# led_schematic.net
KiCad netlist of a schematic drawn in Altium Designer
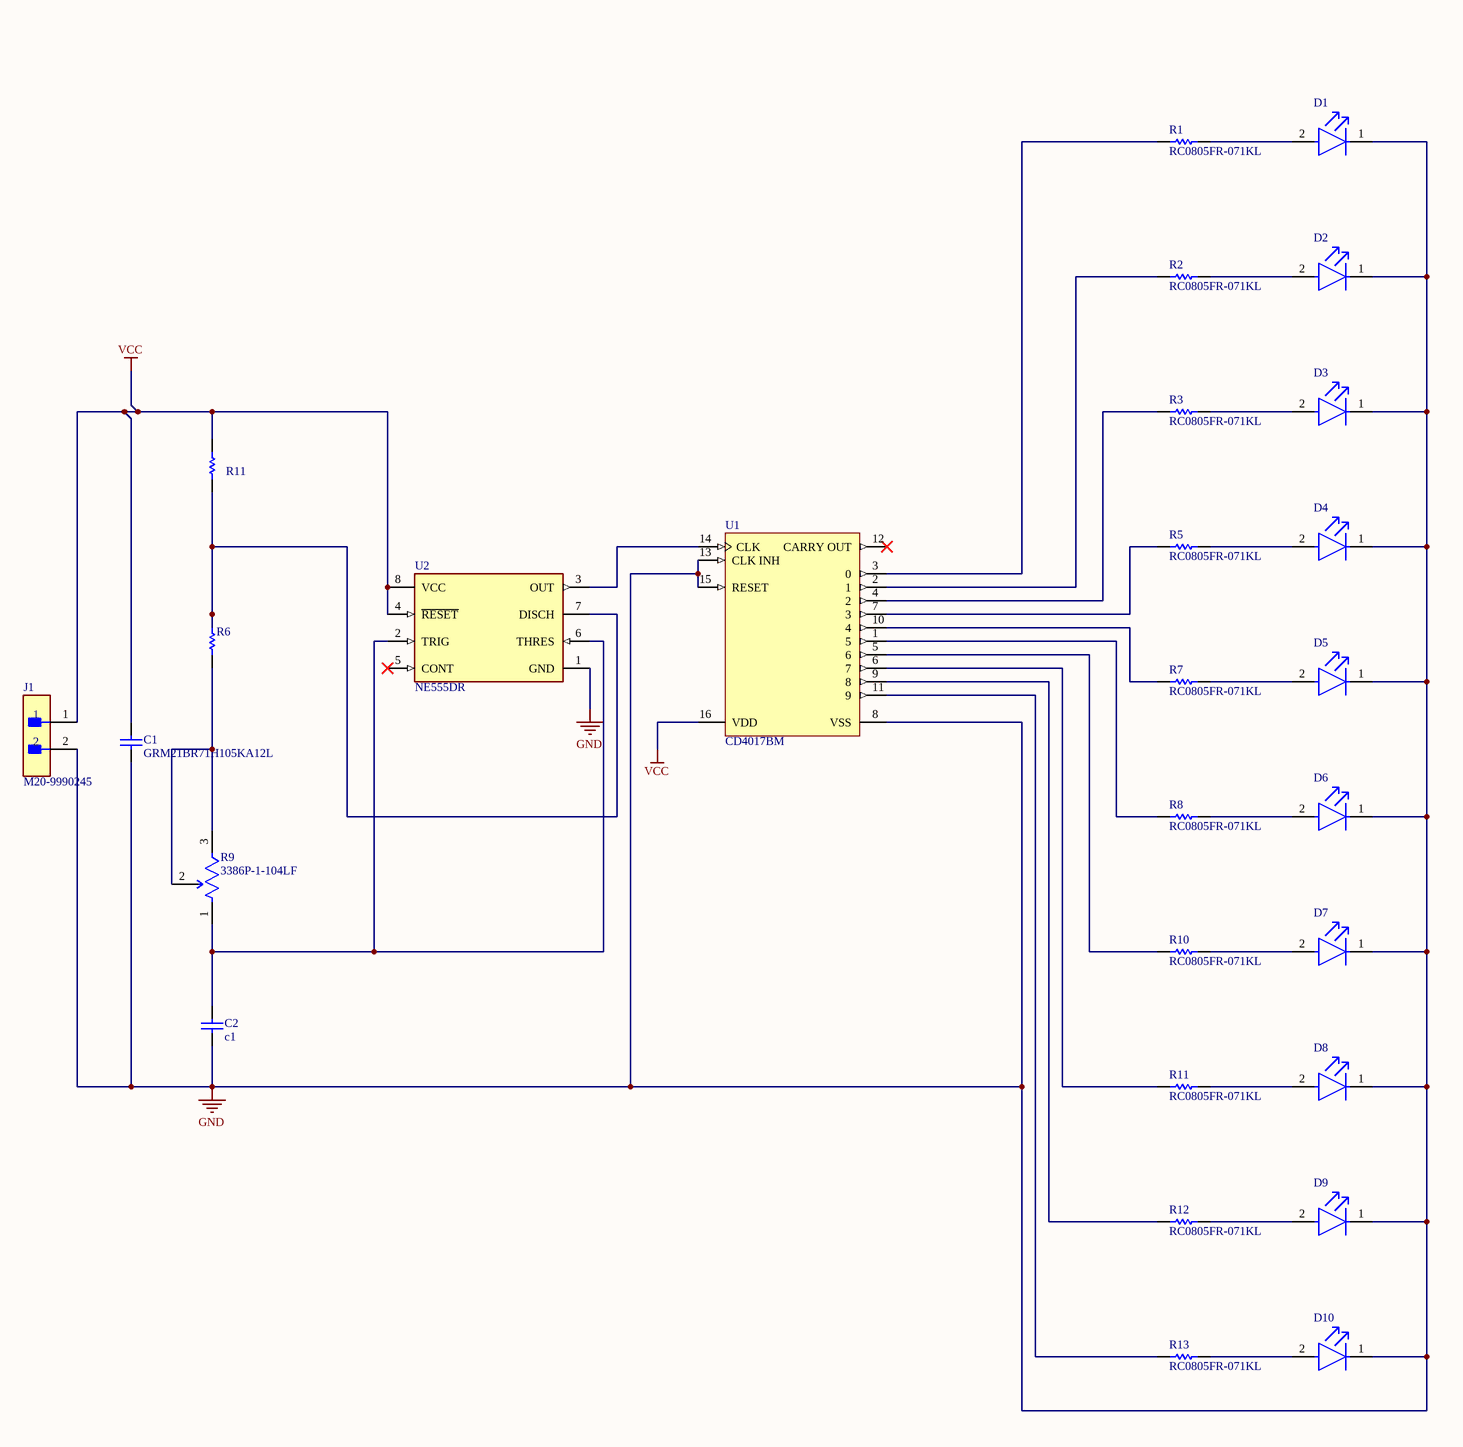
[diagram p0: led_schematic.SchDoc, right]

(export (version "E")
  (design (tool "Eeschema 10.0.6"))
  (components
    (comp (ref "C1")
      (value "GRM21BR71H105KA12L")
      (footprint "CAPC2013X135X45LL10T25")
      (fields (field (name "MANUFACTURER") "Murata"))
      (libsource (lib "Altium Content Vault") (part "CAP"))
    )
    (comp (ref "C2")
      (value "c1")
      (footprint "CAPC2013X135X45LL10T25")
      (fields (field (name "MANUFACTURER") "Murata") (field (name "PART NUMBER") "GRM21BR71H105KA12L"))
      (libsource (lib "Altium Content Vault") (part "CAP"))
    )
    (comp (ref "D1")
      (value "HLMP-1719")
      (footprint "FP-HLMP-1719-MFG")
      (description "LED YELLOW DIFFUSED T-1 T/H")
      (fields
        (field (name "MANUFACTURER") "Broadcom")
        (field (name "OCTOPART") "https://octopart.com/hlmp-1719-broadcom-71130405")
      )
      (libsource (lib "Altium Content Vault") (part "8706943c75ba83719d021d2fdc84c58"))
    )
    (comp (ref "D2")
      (value "HLMP-1719")
      (footprint "FP-HLMP-1719-MFG")
      (description "LED YELLOW DIFFUSED T-1 T/H")
      (fields
        (field (name "MANUFACTURER") "Broadcom")
        (field (name "OCTOPART") "https://octopart.com/hlmp-1719-broadcom-71130405")
      )
      (libsource (lib "Altium Content Vault") (part "8706943c75ba83719d021d2fdc84c58"))
    )
    (comp (ref "D3")
      (value "HLMP-1719")
      (footprint "FP-HLMP-1719-MFG")
      (description "LED YELLOW DIFFUSED T-1 T/H")
      (fields
        (field (name "MANUFACTURER") "Broadcom")
        (field (name "OCTOPART") "https://octopart.com/hlmp-1719-broadcom-71130405")
      )
      (libsource (lib "Altium Content Vault") (part "8706943c75ba83719d021d2fdc84c58"))
    )
    (comp (ref "D4")
      (value "HLMP-1719")
      (footprint "FP-HLMP-1719-MFG")
      (description "LED YELLOW DIFFUSED T-1 T/H")
      (fields
        (field (name "MANUFACTURER") "Broadcom")
        (field (name "OCTOPART") "https://octopart.com/hlmp-1719-broadcom-71130405")
      )
      (libsource (lib "Altium Content Vault") (part "8706943c75ba83719d021d2fdc84c58"))
    )
    (comp (ref "D5")
      (value "HLMP-1719")
      (footprint "FP-HLMP-1719-MFG")
      (description "LED YELLOW DIFFUSED T-1 T/H")
      (fields
        (field (name "MANUFACTURER") "Broadcom")
        (field (name "OCTOPART") "https://octopart.com/hlmp-1719-broadcom-71130405")
      )
      (libsource (lib "Altium Content Vault") (part "8706943c75ba83719d021d2fdc84c58"))
    )
    (comp (ref "D6")
      (value "HLMP-1719")
      (footprint "FP-HLMP-1719-MFG")
      (description "LED YELLOW DIFFUSED T-1 T/H")
      (fields
        (field (name "MANUFACTURER") "Broadcom")
        (field (name "OCTOPART") "https://octopart.com/hlmp-1719-broadcom-71130405")
      )
      (libsource (lib "Altium Content Vault") (part "8706943c75ba83719d021d2fdc84c58"))
    )
    (comp (ref "D7")
      (value "HLMP-1719")
      (footprint "FP-HLMP-1719-MFG")
      (description "LED YELLOW DIFFUSED T-1 T/H")
      (fields
        (field (name "MANUFACTURER") "Broadcom")
        (field (name "OCTOPART") "https://octopart.com/hlmp-1719-broadcom-71130405")
      )
      (libsource (lib "Altium Content Vault") (part "8706943c75ba83719d021d2fdc84c58"))
    )
    (comp (ref "D8")
      (value "HLMP-1719")
      (footprint "FP-HLMP-1719-MFG")
      (description "LED YELLOW DIFFUSED T-1 T/H")
      (fields
        (field (name "MANUFACTURER") "Broadcom")
        (field (name "OCTOPART") "https://octopart.com/hlmp-1719-broadcom-71130405")
      )
      (libsource (lib "Altium Content Vault") (part "8706943c75ba83719d021d2fdc84c58"))
    )
    (comp (ref "D9")
      (value "HLMP-1719")
      (footprint "FP-HLMP-1719-MFG")
      (description "LED YELLOW DIFFUSED T-1 T/H")
      (fields
        (field (name "MANUFACTURER") "Broadcom")
        (field (name "OCTOPART") "https://octopart.com/hlmp-1719-broadcom-71130405")
      )
      (libsource (lib "Altium Content Vault") (part "8706943c75ba83719d021d2fdc84c58"))
    )
    (comp (ref "D10")
      (value "HLMP-1719")
      (footprint "FP-HLMP-1719-MFG")
      (description "LED YELLOW DIFFUSED T-1 T/H")
      (fields
        (field (name "MANUFACTURER") "Broadcom")
        (field (name "OCTOPART") "https://octopart.com/hlmp-1719-broadcom-71130405")
      )
      (libsource (lib "Altium Content Vault") (part "8706943c75ba83719d021d2fdc84c58"))
    )
    (comp (ref "J1")
      (value "M20-9990245")
      (footprint "FP-M20-9990245-MFG")
      (description "CONN HEADER VERT 2POS 2.54MM")
      (fields (field (name "VOLTAGE") "50V"))
      (libsource (lib "Altium Content Vault") (part "3bc925449376181038e59eaffc5286c"))
    )
    (comp (ref "R1")
      (value "RC0805FR-071KL")
      (footprint "RESC2013X60X35ML10T20")
      (description "Chip Resistor, 1 KOhm, +/- 1%, 125 mW, -55 to 155 degC, 0805 (2012 Metric), RoHS, Tape and Reel")
      (fields (field (name "TOLERANCE") "1%") (field (name "MANUFACTURER") "Yageo"))
      (libsource (lib "Altium Content Vault") (part "RES-2"))
    )
    (comp (ref "R2")
      (value "RC0805FR-071KL")
      (footprint "RESC2013X60X35ML10T20")
      (description "Chip Resistor, 1 KOhm, +/- 1%, 125 mW, -55 to 155 degC, 0805 (2012 Metric), RoHS, Tape and Reel")
      (fields (field (name "TOLERANCE") "1%") (field (name "MANUFACTURER") "Yageo"))
      (libsource (lib "Altium Content Vault") (part "RES-2"))
    )
    (comp (ref "R3")
      (value "RC0805FR-071KL")
      (footprint "RESC2013X60X35ML10T20")
      (description "Chip Resistor, 1 KOhm, +/- 1%, 125 mW, -55 to 155 degC, 0805 (2012 Metric), RoHS, Tape and Reel")
      (fields (field (name "TOLERANCE") "1%") (field (name "MANUFACTURER") "Yageo"))
      (libsource (lib "Altium Content Vault") (part "RES-2"))
    )
    (comp (ref "R4")
      (value "R11")
      (footprint "RESC2013X60X35ML10T20")
      (description "Chip Resistor, 1 KOhm, +/- 1%, 125 mW, -55 to 155 degC, 0805 (2012 Metric), RoHS, Tape and Reel")
      (fields (field (name "TOLERANCE") "1%") (field (name "MANUFACTURER") "Yageo"))
      (libsource (lib "Altium Content Vault") (part "RES-2"))
    )
    (comp (ref "R5")
      (value "RC0805FR-071KL")
      (footprint "RESC2013X60X35ML10T20")
      (description "Chip Resistor, 1 KOhm, +/- 1%, 125 mW, -55 to 155 degC, 0805 (2012 Metric), RoHS, Tape and Reel")
      (fields (field (name "TOLERANCE") "1%") (field (name "MANUFACTURER") "Yageo"))
      (libsource (lib "Altium Content Vault") (part "RES-2"))
    )
    (comp (ref "R6")
      (value "RC0805FR-071KL")
      (footprint "RESC2013X60X35ML10T20")
      (description "Chip Resistor, 1 KOhm, +/- 1%, 125 mW, -55 to 155 degC, 0805 (2012 Metric), RoHS, Tape and Reel")
      (fields (field (name "TOLERANCE") "1%") (field (name "MANUFACTURER") "Yageo"))
      (libsource (lib "Altium Content Vault") (part "RES-2"))
    )
    (comp (ref "R7")
      (value "RC0805FR-071KL")
      (footprint "RESC2013X60X35ML10T20")
      (description "Chip Resistor, 1 KOhm, +/- 1%, 125 mW, -55 to 155 degC, 0805 (2012 Metric), RoHS, Tape and Reel")
      (fields (field (name "TOLERANCE") "1%") (field (name "MANUFACTURER") "Yageo"))
      (libsource (lib "Altium Content Vault") (part "RES-2"))
    )
    (comp (ref "R8")
      (value "RC0805FR-071KL")
      (footprint "RESC2013X60X35ML10T20")
      (description "Chip Resistor, 1 KOhm, +/- 1%, 125 mW, -55 to 155 degC, 0805 (2012 Metric), RoHS, Tape and Reel")
      (fields (field (name "TOLERANCE") "1%") (field (name "MANUFACTURER") "Yageo"))
      (libsource (lib "Altium Content Vault") (part "RES-2"))
    )
    (comp (ref "R9")
      (value "3386P-1-104LF")
      (footprint "FP-3386P-MFG")
      (description "TRIMMER 100K OHM 0.5W PC PIN TOP")
      (fields (field (name "TOLERANCE") "10%"))
      (libsource (lib "Altium Content Vault") (part "13357d81287629c2fd191d242cfa50c"))
    )
    (comp (ref "R10")
      (value "RC0805FR-071KL")
      (footprint "RESC2013X60X35ML10T20")
      (description "Chip Resistor, 1 KOhm, +/- 1%, 125 mW, -55 to 155 degC, 0805 (2012 Metric), RoHS, Tape and Reel")
      (fields (field (name "TOLERANCE") "1%") (field (name "MANUFACTURER") "Yageo"))
      (libsource (lib "Altium Content Vault") (part "RES-2"))
    )
    (comp (ref "R11")
      (value "RC0805FR-071KL")
      (footprint "RESC2013X60X35ML10T20")
      (description "Chip Resistor, 1 KOhm, +/- 1%, 125 mW, -55 to 155 degC, 0805 (2012 Metric), RoHS, Tape and Reel")
      (fields (field (name "TOLERANCE") "1%") (field (name "MANUFACTURER") "Yageo"))
      (libsource (lib "Altium Content Vault") (part "RES-2"))
    )
    (comp (ref "R12")
      (value "RC0805FR-071KL")
      (footprint "RESC2013X60X35ML10T20")
      (description "Chip Resistor, 1 KOhm, +/- 1%, 125 mW, -55 to 155 degC, 0805 (2012 Metric), RoHS, Tape and Reel")
      (fields (field (name "TOLERANCE") "1%") (field (name "MANUFACTURER") "Yageo"))
      (libsource (lib "Altium Content Vault") (part "RES-2"))
    )
    (comp (ref "R13")
      (value "RC0805FR-071KL")
      (footprint "RESC2013X60X35ML10T20")
      (description "Chip Resistor, 1 KOhm, +/- 1%, 125 mW, -55 to 155 degC, 0805 (2012 Metric), RoHS, Tape and Reel")
      (fields (field (name "TOLERANCE") "1%") (field (name "MANUFACTURER") "Yageo"))
      (libsource (lib "Altium Content Vault") (part "RES-2"))
    )
    (comp (ref "U1")
      (value "CD4017BM")
      (footprint "D0016A_N")
      (description "CMOS Decade Counter with 10 Decoded Outputs, D0016A, TUBE")
      (fields
        (field (name "GENERIC PART NUMBER") "CD4017B")
        (field (name "MANUFACTURER") "Texas Instruments")
      )
      (libsource (lib "Altium Content Vault") (part "TI-CD4017B-16"))
    )
    (comp (ref "U2")
      (value "NE555DR")
      (footprint "FP-D0008A-IPC_A")
      (description "IC OSC SGL TIMER 100KHZ 8-SOIC")
      (libsource (lib "Altium Content Vault") (part "a29bba90211dec1890110b94dad7d53"))
    )
  )
  (nets
    (net (code "1") (name "GND") (class "Default")
      (node (ref "C1") (pin "1") (pinfunction "1_1") (pintype "passive"))
      (node (ref "C2") (pin "1") (pinfunction "1_1") (pintype "passive"))
      (node (ref "D1") (pin "1") (pinfunction "C_1") (pintype "passive"))
      (node (ref "D10") (pin "1") (pinfunction "C_1") (pintype "passive"))
      (node (ref "D2") (pin "1") (pinfunction "C_1") (pintype "passive"))
      (node (ref "D3") (pin "1") (pinfunction "C_1") (pintype "passive"))
      (node (ref "D4") (pin "1") (pinfunction "C_1") (pintype "passive"))
      (node (ref "D5") (pin "1") (pinfunction "C_1") (pintype "passive"))
      (node (ref "D6") (pin "1") (pinfunction "C_1") (pintype "passive"))
      (node (ref "D7") (pin "1") (pinfunction "C_1") (pintype "passive"))
      (node (ref "D8") (pin "1") (pinfunction "C_1") (pintype "passive"))
      (node (ref "D9") (pin "1") (pinfunction "C_1") (pintype "passive"))
      (node (ref "J1") (pin "2") (pinfunction "2_2") (pintype "passive"))
      (node (ref "U1") (pin "13") (pinfunction "CLK_INH_13") (pintype "input"))
      (node (ref "U1") (pin "15") (pinfunction "RESET_15") (pintype "input"))
      (node (ref "U1") (pin "8") (pinfunction "VSS_8") (pintype "power_in"))
      (node (ref "U2") (pin "1") (pinfunction "GND_1") (pintype "power_in"))
    )
    (net (code "2") (name "Net-(D1-A)") (class "Default")
      (node (ref "D1") (pin "2") (pinfunction "A_2") (pintype "passive"))
      (node (ref "R1") (pin "2") (pinfunction "2_2") (pintype "passive"))
    )
    (net (code "3") (name "Net-(D2-A)") (class "Default")
      (node (ref "D2") (pin "2") (pinfunction "A_2") (pintype "passive"))
      (node (ref "R2") (pin "2") (pinfunction "2_2") (pintype "passive"))
    )
    (net (code "4") (name "Net-(D3-A)") (class "Default")
      (node (ref "D3") (pin "2") (pinfunction "A_2") (pintype "passive"))
      (node (ref "R3") (pin "2") (pinfunction "2_2") (pintype "passive"))
    )
    (net (code "5") (name "Net-(D4-A)") (class "Default")
      (node (ref "D4") (pin "2") (pinfunction "A_2") (pintype "passive"))
      (node (ref "R5") (pin "2") (pinfunction "2_2") (pintype "passive"))
    )
    (net (code "6") (name "Net-(D5-A)") (class "Default")
      (node (ref "D5") (pin "2") (pinfunction "A_2") (pintype "passive"))
      (node (ref "R7") (pin "2") (pinfunction "2_2") (pintype "passive"))
    )
    (net (code "7") (name "Net-(D6-A)") (class "Default")
      (node (ref "D6") (pin "2") (pinfunction "A_2") (pintype "passive"))
      (node (ref "R8") (pin "2") (pinfunction "2_2") (pintype "passive"))
    )
    (net (code "8") (name "Net-(D7-A)") (class "Default")
      (node (ref "D7") (pin "2") (pinfunction "A_2") (pintype "passive"))
      (node (ref "R10") (pin "2") (pinfunction "2_2") (pintype "passive"))
    )
    (net (code "9") (name "Net-(D8-A)") (class "Default")
      (node (ref "D8") (pin "2") (pinfunction "A_2") (pintype "passive"))
      (node (ref "R11") (pin "2") (pinfunction "2_2") (pintype "passive"))
    )
    (net (code "10") (name "Net-(D9-A)") (class "Default")
      (node (ref "D9") (pin "2") (pinfunction "A_2") (pintype "passive"))
      (node (ref "R12") (pin "2") (pinfunction "2_2") (pintype "passive"))
    )
    (net (code "11") (name "Net-(D10-A)") (class "Default")
      (node (ref "D10") (pin "2") (pinfunction "A_2") (pintype "passive"))
      (node (ref "R13") (pin "2") (pinfunction "2_2") (pintype "passive"))
    )
    (net (code "12") (name "Net-(R9-CCW)") (class "Default")
      (node (ref "C2") (pin "2") (pinfunction "2_2") (pintype "passive"))
      (node (ref "R9") (pin "1") (pinfunction "CCW_1") (pintype "passive"))
      (node (ref "U2") (pin "2") (pinfunction "TRIG_2") (pintype "input"))
      (node (ref "U2") (pin "6") (pinfunction "THRES_6") (pintype "input"))
    )
    (net (code "13") (name "Net-(R9-CW)") (class "Default")
      (node (ref "R6") (pin "1") (pinfunction "1_1") (pintype "passive"))
      (node (ref "R9") (pin "2") (pinfunction "WIPER_2") (pintype "passive"))
      (node (ref "R9") (pin "3") (pinfunction "CW_3") (pintype "passive"))
    )
    (net (code "14") (name "Net-(U1-0)") (class "Default")
      (node (ref "R1") (pin "1") (pinfunction "1_1") (pintype "passive"))
      (node (ref "U1") (pin "3") (pinfunction "0_3") (pintype "output"))
    )
    (net (code "15") (name "Net-(U1-1)") (class "Default")
      (node (ref "R2") (pin "1") (pinfunction "1_1") (pintype "passive"))
      (node (ref "U1") (pin "2") (pinfunction "1_2") (pintype "output"))
    )
    (net (code "16") (name "Net-(U1-2)") (class "Default")
      (node (ref "R3") (pin "1") (pinfunction "1_1") (pintype "passive"))
      (node (ref "U1") (pin "4") (pinfunction "2_4") (pintype "output"))
    )
    (net (code "17") (name "Net-(U1-3)") (class "Default")
      (node (ref "R5") (pin "1") (pinfunction "1_1") (pintype "passive"))
      (node (ref "U1") (pin "7") (pinfunction "3_7") (pintype "output"))
    )
    (net (code "18") (name "Net-(U1-4)") (class "Default")
      (node (ref "R7") (pin "1") (pinfunction "1_1") (pintype "passive"))
      (node (ref "U1") (pin "10") (pinfunction "4_10") (pintype "output"))
    )
    (net (code "19") (name "Net-(U1-5)") (class "Default")
      (node (ref "R8") (pin "1") (pinfunction "1_1") (pintype "passive"))
      (node (ref "U1") (pin "1") (pinfunction "5_1") (pintype "output"))
    )
    (net (code "20") (name "Net-(U1-6)") (class "Default")
      (node (ref "R10") (pin "1") (pinfunction "1_1") (pintype "passive"))
      (node (ref "U1") (pin "5") (pinfunction "6_5") (pintype "output"))
    )
    (net (code "21") (name "Net-(U1-7)") (class "Default")
      (node (ref "R11") (pin "1") (pinfunction "1_1") (pintype "passive"))
      (node (ref "U1") (pin "6") (pinfunction "7_6") (pintype "output"))
    )
    (net (code "22") (name "Net-(U1-8)") (class "Default")
      (node (ref "R12") (pin "1") (pinfunction "1_1") (pintype "passive"))
      (node (ref "U1") (pin "9") (pinfunction "8_9") (pintype "output"))
    )
    (net (code "23") (name "Net-(U1-9)") (class "Default")
      (node (ref "R13") (pin "1") (pinfunction "1_1") (pintype "passive"))
      (node (ref "U1") (pin "11") (pinfunction "9_11") (pintype "output"))
    )
    (net (code "24") (name "Net-(U1-CLK)") (class "Default")
      (node (ref "U1") (pin "14") (pinfunction "CLK_14") (pintype "input"))
      (node (ref "U2") (pin "3") (pinfunction "OUT_3") (pintype "output"))
    )
    (net (code "25") (name "Net-(U2-DISCH)") (class "Default")
      (node (ref "R4") (pin "1") (pinfunction "1_1") (pintype "passive"))
      (node (ref "R6") (pin "2") (pinfunction "2_2") (pintype "passive"))
      (node (ref "U2") (pin "7") (pinfunction "DISCH_7") (pintype "open_collector"))
    )
    (net (code "26") (name "VCC") (class "Default")
      (node (ref "C1") (pin "2") (pinfunction "2_2") (pintype "passive"))
      (node (ref "J1") (pin "1") (pinfunction "1_1") (pintype "passive"))
      (node (ref "R4") (pin "2") (pinfunction "2_2") (pintype "passive"))
      (node (ref "U1") (pin "16") (pinfunction "VDD_16") (pintype "power_in"))
      (node (ref "U2") (pin "4") (pinfunction "~{RESET}_4") (pintype "input"))
      (node (ref "U2") (pin "8") (pinfunction "VCC_8") (pintype "power_in"))
    )
    (net (code "27") (name "unconnected-(U1-CARRY_OUT-Pad12)") (class "Default")
      (node (ref "U1") (pin "12") (pinfunction "CARRY_OUT_12") (pintype "output+no_connect"))
    )
    (net (code "28") (name "unconnected-(U2-CONT-Pad5)") (class "Default")
      (node (ref "U2") (pin "5") (pinfunction "CONT_5") (pintype "input+no_connect"))
    )
  )
)
